# furby_shield.net
KiCad netlist of a schematic drawn in EAGLE
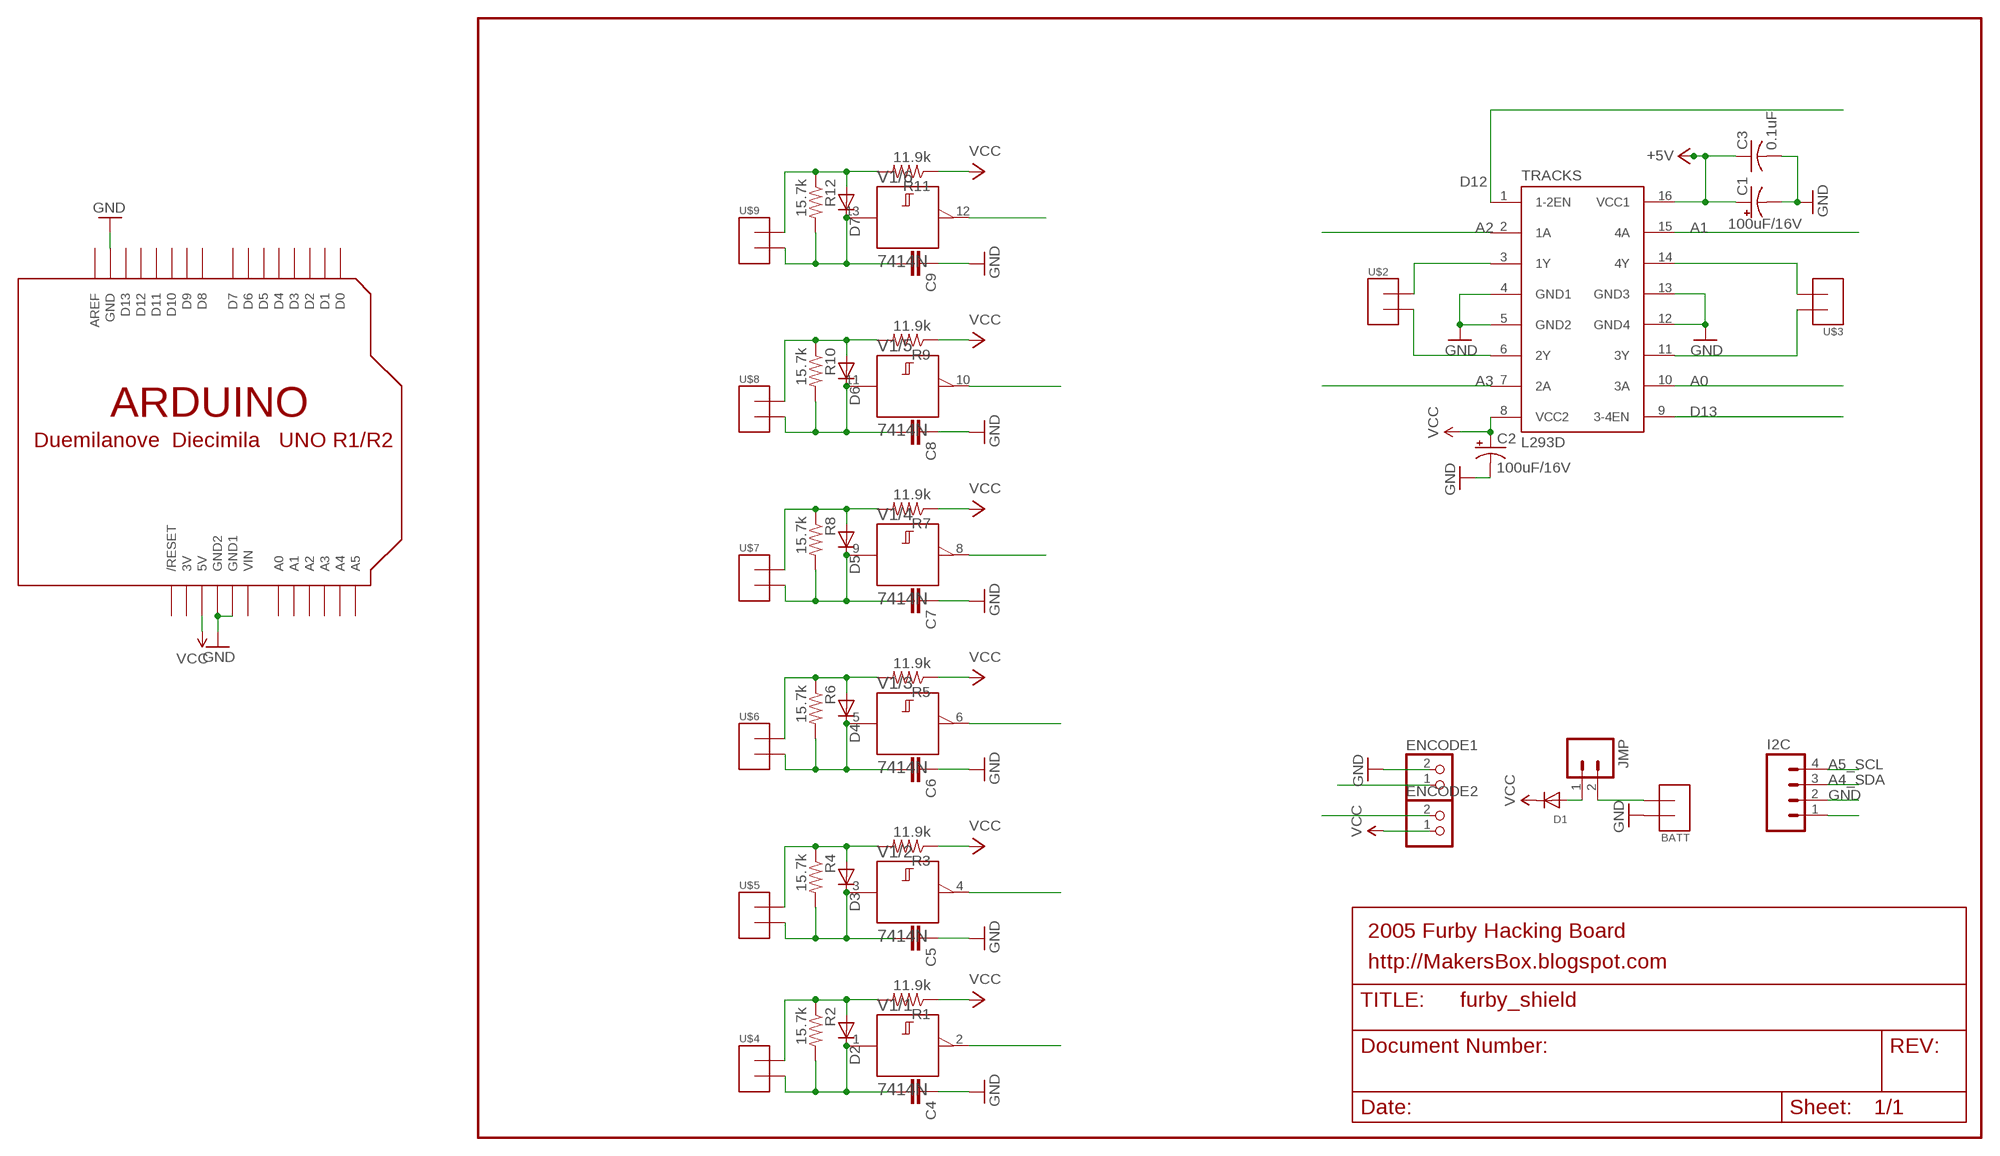
[diagram p0: schematic, sheet 1]

(export (version "E")
  (design (tool "Eeschema 10.0.6"))
  (components
    (comp (ref "BATT")
      (value "TERMINAL2")
      (footprint "eagle-import:TERMINAL_2")
      (libsource (lib "eagle-import") (part "TERMINAL2"))
    )
    (comp (ref "C1")
      (value "100uF/16V")
      (footprint "eagle-import:E2,5-6")
      (libsource (lib "eagle-import") (part "CPOL-USE2.5-6"))
    )
    (comp (ref "C2")
      (value "100uF/16V")
      (footprint "eagle-import:E2,5-6")
      (libsource (lib "eagle-import") (part "CPOL-USE2.5-6"))
    )
    (comp (ref "C3")
      (value "0.1uF")
      (footprint "eagle-import:C025-025X050")
      (libsource (lib "eagle-import") (part "C-US025-025X050"))
    )
    (comp (ref "C4")
      (value "CAPPTH")
      (footprint "eagle-import:CAP-PTH-SMALL")
      (libsource (lib "eagle-import") (part "CAPPTH"))
    )
    (comp (ref "C5")
      (value "CAPPTH")
      (footprint "eagle-import:CAP-PTH-SMALL")
      (libsource (lib "eagle-import") (part "CAPPTH"))
    )
    (comp (ref "C6")
      (value "CAPPTH")
      (footprint "eagle-import:CAP-PTH-SMALL")
      (libsource (lib "eagle-import") (part "CAPPTH"))
    )
    (comp (ref "C7")
      (value "CAPPTH")
      (footprint "eagle-import:CAP-PTH-SMALL")
      (libsource (lib "eagle-import") (part "CAPPTH"))
    )
    (comp (ref "C8")
      (value "CAPPTH")
      (footprint "eagle-import:CAP-PTH-SMALL")
      (libsource (lib "eagle-import") (part "CAPPTH"))
    )
    (comp (ref "C9")
      (value "CAPPTH")
      (footprint "eagle-import:CAP-PTH-SMALL")
      (libsource (lib "eagle-import") (part "CAPPTH"))
    )
    (comp (ref "D1")
      (value "DIODEDO-1N4148")
      (footprint "eagle-import:DO-1N4148")
      (libsource (lib "eagle-import") (part "DIODEDO-1N4148"))
    )
    (comp (ref "D2")
      (value "DIODE-D-2.5")
      (footprint "eagle-import:D-2.5")
      (libsource (lib "eagle-import") (part "DIODE-D-2.5"))
    )
    (comp (ref "D3")
      (value "DIODE-D-2.5")
      (footprint "eagle-import:D-2.5")
      (libsource (lib "eagle-import") (part "DIODE-D-2.5"))
    )
    (comp (ref "D4")
      (value "DIODE-D-2.5")
      (footprint "eagle-import:D-2.5")
      (libsource (lib "eagle-import") (part "DIODE-D-2.5"))
    )
    (comp (ref "D5")
      (value "DIODE-D-2.5")
      (footprint "eagle-import:D-2.5")
      (libsource (lib "eagle-import") (part "DIODE-D-2.5"))
    )
    (comp (ref "D6")
      (value "DIODE-D-2.5")
      (footprint "eagle-import:D-2.5")
      (libsource (lib "eagle-import") (part "DIODE-D-2.5"))
    )
    (comp (ref "D7")
      (value "DIODE-D-2.5")
      (footprint "eagle-import:D-2.5")
      (libsource (lib "eagle-import") (part "DIODE-D-2.5"))
    )
    (comp (ref "ENCODE1")
      (value "JST_2PIN-THM")
      (footprint "eagle-import:JST-PH-2-THM")
      (libsource (lib "eagle-import") (part "JST_2PIN-THM"))
    )
    (comp (ref "ENCODE2")
      (value "JST_2PIN-THM")
      (footprint "eagle-import:JST-PH-2-THM")
      (libsource (lib "eagle-import") (part "JST_2PIN-THM"))
    )
    (comp (ref "I2C")
      (value "M04PTH")
      (footprint "eagle-import:1X04")
      (libsource (lib "eagle-import") (part "M04PTH"))
    )
    (comp (ref "JMP")
      (value "M02PTH")
      (footprint "eagle-import:1X02")
      (libsource (lib "eagle-import") (part "M02PTH"))
    )
    (comp (ref "R1")
      (value "11.9k")
      (footprint "eagle-import:0204V")
      (libsource (lib "eagle-import") (part "R-US_0204/2V"))
    )
    (comp (ref "R2")
      (value "15.7k")
      (footprint "eagle-import:0204V")
      (libsource (lib "eagle-import") (part "R-US_0204/2V"))
    )
    (comp (ref "R3")
      (value "11.9k")
      (footprint "eagle-import:0204V")
      (libsource (lib "eagle-import") (part "R-US_0204/2V"))
    )
    (comp (ref "R4")
      (value "15.7k")
      (footprint "eagle-import:0204V")
      (libsource (lib "eagle-import") (part "R-US_0204/2V"))
    )
    (comp (ref "R5")
      (value "11.9k")
      (footprint "eagle-import:0204V")
      (libsource (lib "eagle-import") (part "R-US_0204/2V"))
    )
    (comp (ref "R6")
      (value "15.7k")
      (footprint "eagle-import:0204V")
      (libsource (lib "eagle-import") (part "R-US_0204/2V"))
    )
    (comp (ref "R7")
      (value "11.9k")
      (footprint "eagle-import:0204V")
      (libsource (lib "eagle-import") (part "R-US_0204/2V"))
    )
    (comp (ref "R8")
      (value "15.7k")
      (footprint "eagle-import:0204V")
      (libsource (lib "eagle-import") (part "R-US_0204/2V"))
    )
    (comp (ref "R9")
      (value "11.9k")
      (footprint "eagle-import:0204V")
      (libsource (lib "eagle-import") (part "R-US_0204/2V"))
    )
    (comp (ref "R10")
      (value "15.7k")
      (footprint "eagle-import:0204V")
      (libsource (lib "eagle-import") (part "R-US_0204/2V"))
    )
    (comp (ref "R11")
      (value "11.9k")
      (footprint "eagle-import:0204V")
      (libsource (lib "eagle-import") (part "R-US_0204/2V"))
    )
    (comp (ref "R12")
      (value "15.7k")
      (footprint "eagle-import:0204V")
      (libsource (lib "eagle-import") (part "R-US_0204/2V"))
    )
    (comp (ref "TRACKS")
      (value "L293D")
      (footprint "eagle-import:DIL16")
      (libsource (lib "eagle-import") (part "L293E"))
    )
    (comp (ref "U$1")
      (value "ARDUINO-BPLACE")
      (footprint "eagle-import:ARDUINO-BPLACE")
      (libsource (lib "eagle-import") (part "ARDUINO-BPLACE"))
    )
    (comp (ref "U$2")
      (value "TERMINAL2")
      (footprint "eagle-import:TERMINAL_2")
      (libsource (lib "eagle-import") (part "TERMINAL2"))
    )
    (comp (ref "U$3")
      (value "TERMINAL2")
      (footprint "eagle-import:TERMINAL_2")
      (libsource (lib "eagle-import") (part "TERMINAL2"))
    )
    (comp (ref "U$4")
      (value "TERMINAL2")
      (footprint "eagle-import:TERMINAL_2")
      (libsource (lib "eagle-import") (part "TERMINAL2"))
    )
    (comp (ref "U$5")
      (value "TERMINAL2")
      (footprint "eagle-import:TERMINAL_2")
      (libsource (lib "eagle-import") (part "TERMINAL2"))
    )
    (comp (ref "U$6")
      (value "TERMINAL2")
      (footprint "eagle-import:TERMINAL_2")
      (libsource (lib "eagle-import") (part "TERMINAL2"))
    )
    (comp (ref "U$7")
      (value "TERMINAL2")
      (footprint "eagle-import:TERMINAL_2")
      (libsource (lib "eagle-import") (part "TERMINAL2"))
    )
    (comp (ref "U$8")
      (value "TERMINAL2")
      (footprint "eagle-import:TERMINAL_2")
      (libsource (lib "eagle-import") (part "TERMINAL2"))
    )
    (comp (ref "U$9")
      (value "TERMINAL2")
      (footprint "eagle-import:TERMINAL_2")
      (libsource (lib "eagle-import") (part "TERMINAL2"))
    )
    (comp (ref "V1")
      (value "7414N")
      (footprint "eagle-import:DIL14")
      (libsource (lib "eagle-import") (part "7414N"))
    )
  )
  (nets
    (net (code "1") (name "+5V") (class "Default")
      (node (ref "C1") (pin "+") (pinfunction "+_+") (pintype "passive"))
      (node (ref "C3") (pin "1") (pinfunction "1_1") (pintype "passive"))
      (node (ref "TRACKS") (pin "16") (pinfunction "VCC1_16") (pintype "power_in"))
    )
    (net (code "2") (name "/3V") (class "Default")
      (node (ref "U$1") (pin "3V") (pinfunction "3V_3V") (pintype "power_in"))
    )
    (net (code "3") (name "/A0") (class "Default")
      (node (ref "TRACKS") (pin "10") (pinfunction "3A_10") (pintype "input"))
    )
    (net (code "4") (name "/A1") (class "Default")
      (node (ref "TRACKS") (pin "15") (pinfunction "4A_15") (pintype "input"))
    )
    (net (code "5") (name "/A2") (class "Default")
      (node (ref "TRACKS") (pin "2") (pinfunction "1A_2") (pintype "input"))
    )
    (net (code "6") (name "/A3") (class "Default")
      (node (ref "TRACKS") (pin "7") (pinfunction "2A_7") (pintype "input"))
    )
    (net (code "7") (name "/A4_SDA") (class "Default")
      (node (ref "I2C") (pin "3") (pinfunction "3_3") (pintype "passive"))
    )
    (net (code "8") (name "/A5_SCL") (class "Default")
      (node (ref "I2C") (pin "4") (pinfunction "4_4") (pintype "passive"))
    )
    (net (code "9") (name "/D12") (class "Default")
      (node (ref "TRACKS") (pin "1") (pinfunction "1-2EN_1") (pintype "input"))
    )
    (net (code "10") (name "/D13") (class "Default")
      (node (ref "TRACKS") (pin "9") (pinfunction "3-4EN_9") (pintype "input"))
    )
    (net (code "11") (name "/VIN") (class "Default")
      (node (ref "U$1") (pin "VIN") (pinfunction "VIN_VIN") (pintype "power_in"))
    )
    (net (code "12") (name "GND") (class "Default")
      (node (ref "BATT") (pin "P$1") (pinfunction "P$1_P$1") (pintype "bidirectional"))
      (node (ref "C1") (pin "-") (pinfunction "-_-") (pintype "passive"))
      (node (ref "C2") (pin "-") (pinfunction "-_-") (pintype "passive"))
      (node (ref "C3") (pin "2") (pinfunction "2_2") (pintype "passive"))
      (node (ref "C4") (pin "1") (pinfunction "1_1") (pintype "passive"))
      (node (ref "C5") (pin "1") (pinfunction "1_1") (pintype "passive"))
      (node (ref "C6") (pin "1") (pinfunction "1_1") (pintype "passive"))
      (node (ref "C7") (pin "1") (pinfunction "1_1") (pintype "passive"))
      (node (ref "C8") (pin "1") (pinfunction "1_1") (pintype "passive"))
      (node (ref "C9") (pin "1") (pinfunction "1_1") (pintype "passive"))
      (node (ref "ENCODE1") (pin "2") (pinfunction "1_2") (pintype "passive"))
      (node (ref "I2C") (pin "2") (pinfunction "2_2") (pintype "passive"))
      (node (ref "TRACKS") (pin "12") (pinfunction "GND4_12") (pintype "power_in"))
      (node (ref "TRACKS") (pin "13") (pinfunction "GND3_13") (pintype "power_in"))
      (node (ref "TRACKS") (pin "4") (pinfunction "GND1_4") (pintype "power_in"))
      (node (ref "TRACKS") (pin "5") (pinfunction "GND2_5") (pintype "power_in"))
      (node (ref "U$1") (pin "GND") (pinfunction "GND_GND") (pintype "power_in"))
      (node (ref "U$1") (pin "GND1") (pinfunction "GND1_GND1") (pintype "power_in"))
      (node (ref "U$1") (pin "GND2") (pinfunction "GND2_GND2") (pintype "power_in"))
    )
    (net (code "13") (name "Net-(BATT-PadP$2)") (class "Default")
      (node (ref "BATT") (pin "P$2") (pinfunction "P$2_P$2") (pintype "bidirectional"))
      (node (ref "JMP") (pin "2") (pinfunction "2_2") (pintype "passive"))
    )
    (net (code "14") (name "Net-(D1-PadA)") (class "Default")
      (node (ref "D1") (pin "A") (pinfunction "A_A") (pintype "passive"))
      (node (ref "JMP") (pin "1") (pinfunction "1_1") (pintype "passive"))
    )
    (net (code "15") (name "Net-(D2-PadA)") (class "Default")
      (node (ref "D2") (pin "A") (pinfunction "A_A") (pintype "passive"))
      (node (ref "R1") (pin "2") (pinfunction "2_2") (pintype "passive"))
      (node (ref "R2") (pin "1") (pinfunction "1_1") (pintype "passive"))
      (node (ref "U$4") (pin "P$1") (pinfunction "P$1_P$1") (pintype "bidirectional"))
    )
    (net (code "16") (name "Net-(D3-PadA)") (class "Default")
      (node (ref "D3") (pin "A") (pinfunction "A_A") (pintype "passive"))
      (node (ref "R3") (pin "2") (pinfunction "2_2") (pintype "passive"))
      (node (ref "R4") (pin "1") (pinfunction "1_1") (pintype "passive"))
      (node (ref "U$5") (pin "P$1") (pinfunction "P$1_P$1") (pintype "bidirectional"))
    )
    (net (code "17") (name "Net-(D4-PadA)") (class "Default")
      (node (ref "D4") (pin "A") (pinfunction "A_A") (pintype "passive"))
      (node (ref "R5") (pin "2") (pinfunction "2_2") (pintype "passive"))
      (node (ref "R6") (pin "1") (pinfunction "1_1") (pintype "passive"))
      (node (ref "U$6") (pin "P$1") (pinfunction "P$1_P$1") (pintype "bidirectional"))
    )
    (net (code "18") (name "Net-(D5-PadA)") (class "Default")
      (node (ref "D5") (pin "A") (pinfunction "A_A") (pintype "passive"))
      (node (ref "R7") (pin "2") (pinfunction "2_2") (pintype "passive"))
      (node (ref "R8") (pin "1") (pinfunction "1_1") (pintype "passive"))
      (node (ref "U$7") (pin "P$1") (pinfunction "P$1_P$1") (pintype "bidirectional"))
    )
    (net (code "19") (name "Net-(D6-PadA)") (class "Default")
      (node (ref "D6") (pin "A") (pinfunction "A_A") (pintype "passive"))
      (node (ref "R10") (pin "1") (pinfunction "1_1") (pintype "passive"))
      (node (ref "R9") (pin "2") (pinfunction "2_2") (pintype "passive"))
      (node (ref "U$8") (pin "P$1") (pinfunction "P$1_P$1") (pintype "bidirectional"))
    )
    (net (code "20") (name "Net-(D7-PadA)") (class "Default")
      (node (ref "D7") (pin "A") (pinfunction "A_A") (pintype "passive"))
      (node (ref "R11") (pin "2") (pinfunction "2_2") (pintype "passive"))
      (node (ref "R12") (pin "1") (pinfunction "1_1") (pintype "passive"))
      (node (ref "U$9") (pin "P$1") (pinfunction "P$1_P$1") (pintype "bidirectional"))
    )
    (net (code "21") (name "Net-(TRACKS-1Y)") (class "Default")
      (node (ref "TRACKS") (pin "3") (pinfunction "1Y_3") (pintype "output"))
      (node (ref "U$2") (pin "P$1") (pinfunction "P$1_P$1") (pintype "bidirectional"))
    )
    (net (code "22") (name "Net-(TRACKS-2Y)") (class "Default")
      (node (ref "TRACKS") (pin "6") (pinfunction "2Y_6") (pintype "output"))
      (node (ref "U$2") (pin "P$2") (pinfunction "P$2_P$2") (pintype "bidirectional"))
    )
    (net (code "23") (name "Net-(TRACKS-3Y)") (class "Default")
      (node (ref "TRACKS") (pin "11") (pinfunction "3Y_11") (pintype "output"))
      (node (ref "U$3") (pin "P$1") (pinfunction "P$1_P$1") (pintype "bidirectional"))
    )
    (net (code "24") (name "Net-(TRACKS-4Y)") (class "Default")
      (node (ref "TRACKS") (pin "14") (pinfunction "4Y_14") (pintype "output"))
      (node (ref "U$3") (pin "P$2") (pinfunction "P$2_P$2") (pintype "bidirectional"))
    )
    (net (code "25") (name "Net-(V1C-A)") (class "Default")
      (node (ref "C4") (pin "2") (pinfunction "2_2") (pintype "passive"))
      (node (ref "D2") (pin "C") (pinfunction "C_C") (pintype "passive"))
      (node (ref "R2") (pin "2") (pinfunction "2_2") (pintype "passive"))
      (node (ref "U$4") (pin "P$2") (pinfunction "P$2_P$2") (pintype "bidirectional"))
      (node (ref "V1") (pin "1") (pinfunction "A_1") (pintype "input"))
    )
    (net (code "26") (name "Net-(V1D-A)") (class "Default")
      (node (ref "C5") (pin "2") (pinfunction "2_2") (pintype "passive"))
      (node (ref "D3") (pin "C") (pinfunction "C_C") (pintype "passive"))
      (node (ref "R4") (pin "2") (pinfunction "2_2") (pintype "passive"))
      (node (ref "U$5") (pin "P$2") (pinfunction "P$2_P$2") (pintype "bidirectional"))
      (node (ref "V1") (pin "3") (pinfunction "A_3") (pintype "input"))
    )
    (net (code "27") (name "Net-(V1E-A)") (class "Default")
      (node (ref "C6") (pin "2") (pinfunction "2_2") (pintype "passive"))
      (node (ref "D4") (pin "C") (pinfunction "C_C") (pintype "passive"))
      (node (ref "R6") (pin "2") (pinfunction "2_2") (pintype "passive"))
      (node (ref "U$6") (pin "P$2") (pinfunction "P$2_P$2") (pintype "bidirectional"))
      (node (ref "V1") (pin "5") (pinfunction "A_5") (pintype "input"))
    )
    (net (code "28") (name "Net-(V1F-A)") (class "Default")
      (node (ref "C7") (pin "2") (pinfunction "2_2") (pintype "passive"))
      (node (ref "D5") (pin "C") (pinfunction "C_C") (pintype "passive"))
      (node (ref "R8") (pin "2") (pinfunction "2_2") (pintype "passive"))
      (node (ref "U$7") (pin "P$2") (pinfunction "P$2_P$2") (pintype "bidirectional"))
      (node (ref "V1") (pin "9") (pinfunction "A_9") (pintype "input"))
    )
    (net (code "29") (name "Net-(V1G-A)") (class "Default")
      (node (ref "C8") (pin "2") (pinfunction "2_2") (pintype "passive"))
      (node (ref "D6") (pin "C") (pinfunction "C_C") (pintype "passive"))
      (node (ref "R10") (pin "2") (pinfunction "2_2") (pintype "passive"))
      (node (ref "U$8") (pin "P$2") (pinfunction "P$2_P$2") (pintype "bidirectional"))
      (node (ref "V1") (pin "11") (pinfunction "A_11") (pintype "input"))
    )
    (net (code "30") (name "Net-(V1H-A)") (class "Default")
      (node (ref "C9") (pin "2") (pinfunction "2_2") (pintype "passive"))
      (node (ref "D7") (pin "C") (pinfunction "C_C") (pintype "passive"))
      (node (ref "R12") (pin "2") (pinfunction "2_2") (pintype "passive"))
      (node (ref "U$9") (pin "P$2") (pinfunction "P$2_P$2") (pintype "bidirectional"))
      (node (ref "V1") (pin "13") (pinfunction "A_13") (pintype "input"))
    )
    (net (code "31") (name "VCC") (class "Default")
      (node (ref "C2") (pin "+") (pinfunction "+_+") (pintype "passive"))
      (node (ref "D1") (pin "C") (pinfunction "C_C") (pintype "passive"))
      (node (ref "ENCODE2") (pin "1") (pinfunction "2_1") (pintype "passive"))
      (node (ref "R1") (pin "1") (pinfunction "1_1") (pintype "passive"))
      (node (ref "R11") (pin "1") (pinfunction "1_1") (pintype "passive"))
      (node (ref "R3") (pin "1") (pinfunction "1_1") (pintype "passive"))
      (node (ref "R5") (pin "1") (pinfunction "1_1") (pintype "passive"))
      (node (ref "R7") (pin "1") (pinfunction "1_1") (pintype "passive"))
      (node (ref "R9") (pin "1") (pinfunction "1_1") (pintype "passive"))
      (node (ref "TRACKS") (pin "8") (pinfunction "VCC2_8") (pintype "power_in"))
      (node (ref "U$1") (pin "5V") (pinfunction "5V_5V") (pintype "power_in"))
    )
    (net (code "32") (name "unconnected-(ENCODE1-2-Pad1)") (class "Default")
      (node (ref "ENCODE1") (pin "1") (pinfunction "2_1") (pintype "passive"))
    )
    (net (code "33") (name "unconnected-(ENCODE2-1-Pad2)") (class "Default")
      (node (ref "ENCODE2") (pin "2") (pinfunction "1_2") (pintype "passive"))
    )
    (net (code "34") (name "unconnected-(I2C-Pad1)") (class "Default")
      (node (ref "I2C") (pin "1") (pinfunction "1_1") (pintype "passive"))
    )
    (net (code "35") (name "unconnected-(U$1-PadA0)") (class "Default")
      (node (ref "U$1") (pin "A0") (pinfunction "A0_A0") (pintype "bidirectional"))
    )
    (net (code "36") (name "unconnected-(U$1-PadA1)") (class "Default")
      (node (ref "U$1") (pin "A1") (pinfunction "A1_A1") (pintype "bidirectional"))
    )
    (net (code "37") (name "unconnected-(U$1-PadA2)") (class "Default")
      (node (ref "U$1") (pin "A2") (pinfunction "A2_A2") (pintype "bidirectional"))
    )
    (net (code "38") (name "unconnected-(U$1-PadA3)") (class "Default")
      (node (ref "U$1") (pin "A3") (pinfunction "A3_A3") (pintype "bidirectional"))
    )
    (net (code "39") (name "unconnected-(U$1-PadA4)") (class "Default")
      (node (ref "U$1") (pin "A4") (pinfunction "A4_A4") (pintype "bidirectional"))
    )
    (net (code "40") (name "unconnected-(U$1-PadA5)") (class "Default")
      (node (ref "U$1") (pin "A5") (pinfunction "A5_A5") (pintype "bidirectional"))
    )
    (net (code "41") (name "unconnected-(U$1-PadAREF)") (class "Default")
      (node (ref "U$1") (pin "AREF") (pinfunction "AREF_AREF") (pintype "bidirectional"))
    )
    (net (code "42") (name "unconnected-(U$1-PadD0)") (class "Default")
      (node (ref "U$1") (pin "D0") (pinfunction "D0_D0") (pintype "bidirectional"))
    )
    (net (code "43") (name "unconnected-(U$1-PadD1)") (class "Default")
      (node (ref "U$1") (pin "D1") (pinfunction "D1_D1") (pintype "bidirectional"))
    )
    (net (code "44") (name "unconnected-(U$1-PadD2)") (class "Default")
      (node (ref "U$1") (pin "D2") (pinfunction "D2_D2") (pintype "bidirectional"))
    )
    (net (code "45") (name "unconnected-(U$1-PadD3)") (class "Default")
      (node (ref "U$1") (pin "D3") (pinfunction "D3_D3") (pintype "bidirectional"))
    )
    (net (code "46") (name "unconnected-(U$1-PadD4)") (class "Default")
      (node (ref "U$1") (pin "D4") (pinfunction "D4_D4") (pintype "bidirectional"))
    )
    (net (code "47") (name "unconnected-(U$1-PadD5)") (class "Default")
      (node (ref "U$1") (pin "D5") (pinfunction "D5_D5") (pintype "bidirectional"))
    )
    (net (code "48") (name "unconnected-(U$1-PadD6)") (class "Default")
      (node (ref "U$1") (pin "D6") (pinfunction "D6_D6") (pintype "bidirectional"))
    )
    (net (code "49") (name "unconnected-(U$1-PadD7)") (class "Default")
      (node (ref "U$1") (pin "D7") (pinfunction "D7_D7") (pintype "bidirectional"))
    )
    (net (code "50") (name "unconnected-(U$1-PadD8)") (class "Default")
      (node (ref "U$1") (pin "D8") (pinfunction "D8_D8") (pintype "bidirectional"))
    )
    (net (code "51") (name "unconnected-(U$1-PadD9)") (class "Default")
      (node (ref "U$1") (pin "D9") (pinfunction "D9_D9") (pintype "bidirectional"))
    )
    (net (code "52") (name "unconnected-(U$1-PadD10)") (class "Default")
      (node (ref "U$1") (pin "D10") (pinfunction "D10_D10") (pintype "bidirectional"))
    )
    (net (code "53") (name "unconnected-(U$1-PadD11)") (class "Default")
      (node (ref "U$1") (pin "D11") (pinfunction "D11_D11") (pintype "bidirectional"))
    )
    (net (code "54") (name "unconnected-(U$1-PadD12)") (class "Default")
      (node (ref "U$1") (pin "D12") (pinfunction "D12_D12") (pintype "bidirectional"))
    )
    (net (code "55") (name "unconnected-(U$1-PadD13)") (class "Default")
      (node (ref "U$1") (pin "D13") (pinfunction "D13_D13") (pintype "bidirectional"))
    )
    (net (code "56") (name "unconnected-(U$1-{slash}RESET-PadRESET)") (class "Default")
      (node (ref "U$1") (pin "RESET") (pinfunction "/RESET_RESET") (pintype "bidirectional"))
    )
    (net (code "57") (name "unconnected-(V1C-Y-Pad2)") (class "Default")
      (node (ref "V1") (pin "2") (pinfunction "Y_2") (pintype "output"))
    )
    (net (code "58") (name "unconnected-(V1D-Y-Pad4)") (class "Default")
      (node (ref "V1") (pin "4") (pinfunction "Y_4") (pintype "output"))
    )
    (net (code "59") (name "unconnected-(V1E-Y-Pad6)") (class "Default")
      (node (ref "V1") (pin "6") (pinfunction "Y_6") (pintype "output"))
    )
    (net (code "60") (name "unconnected-(V1F-Y-Pad8)") (class "Default")
      (node (ref "V1") (pin "8") (pinfunction "Y_8") (pintype "output"))
    )
    (net (code "61") (name "unconnected-(V1G-Y-Pad10)") (class "Default")
      (node (ref "V1") (pin "10") (pinfunction "Y_10") (pintype "output"))
    )
    (net (code "62") (name "unconnected-(V1H-Y-Pad12)") (class "Default")
      (node (ref "V1") (pin "12") (pinfunction "Y_12") (pintype "output"))
    )
  )
)
